# ST_LINK_V2.net
KiCad netlist of a schematic drawn in Altium Designer
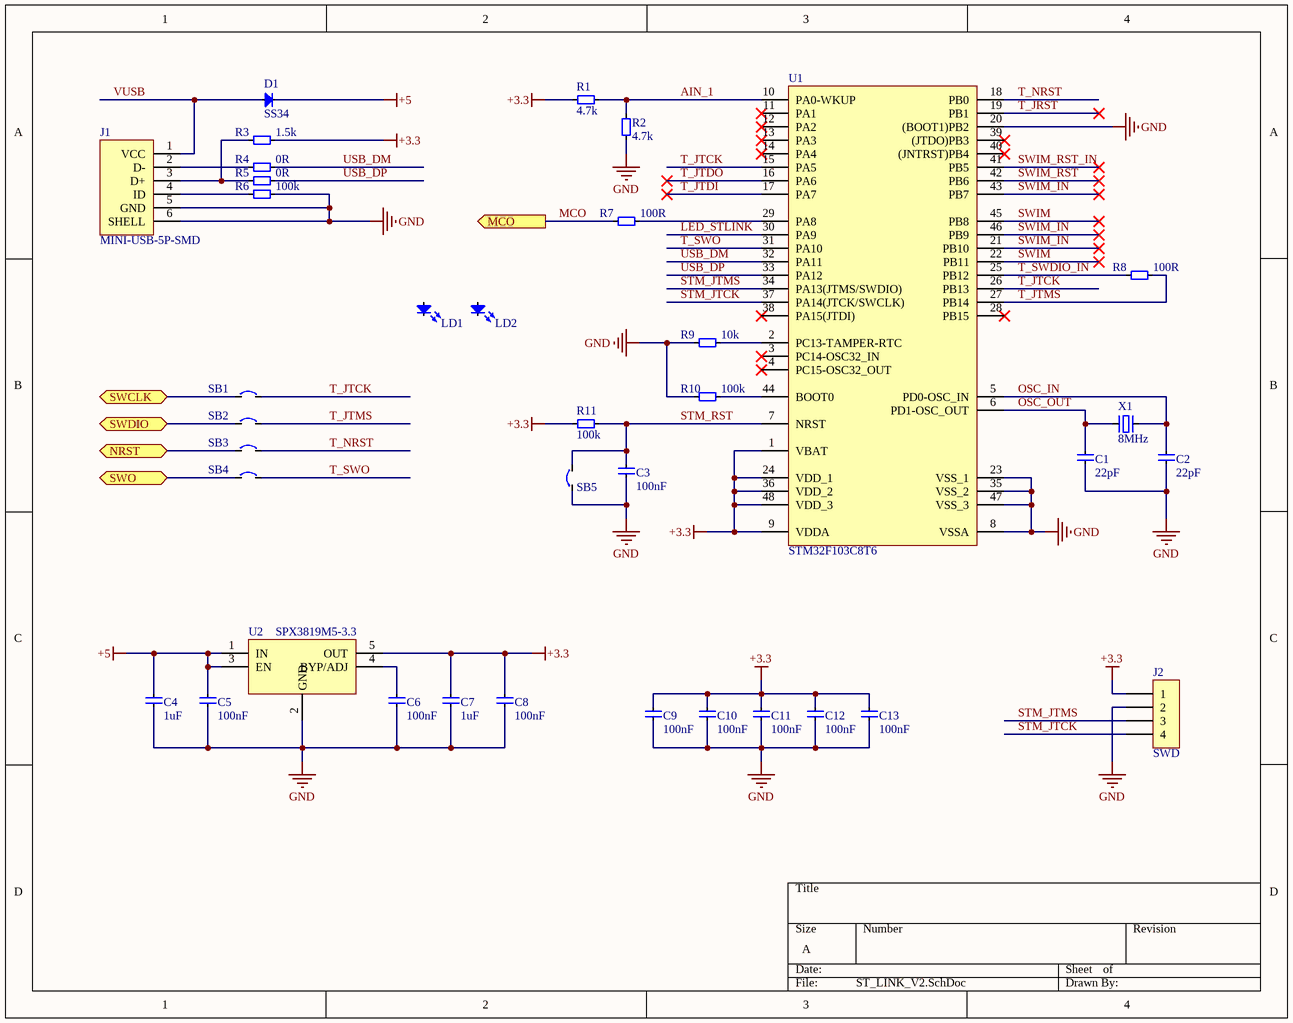
[diagram p0: ST_LINK_V2.SchDoc]

(export (version "E")
  (design (tool "Eeschema 10.0.6"))
  (components
    (comp (ref "C1")
      (value "22pF")
      (footprint "C0805")
      (description "Cac Loai Tu Khong Phan Cuc")
      (libsource (lib "phatvu1294_Lib") (part "CAP"))
    )
    (comp (ref "C2")
      (value "22pF")
      (footprint "C0805")
      (description "Cac Loai Tu Khong Phan Cuc")
      (libsource (lib "phatvu1294_Lib") (part "CAP"))
    )
    (comp (ref "C3")
      (value "100nF")
      (footprint "C0805")
      (description "Cac Loai Tu Khong Phan Cuc")
      (libsource (lib "phatvu1294_Lib") (part "CAP"))
    )
    (comp (ref "C4")
      (value "1uF")
      (footprint "C1206")
      (description "Cac Loai Tu Khong Phan Cuc")
      (libsource (lib "phatvu1294_Lib") (part "CAP"))
    )
    (comp (ref "C5")
      (value "100nF")
      (footprint "C0805")
      (description "Cac Loai Tu Khong Phan Cuc")
      (libsource (lib "phatvu1294_Lib") (part "CAP"))
    )
    (comp (ref "C6")
      (value "100nF")
      (footprint "C0805")
      (description "Cac Loai Tu Khong Phan Cuc")
      (libsource (lib "phatvu1294_Lib") (part "CAP"))
    )
    (comp (ref "C7")
      (value "1uF")
      (footprint "C1206")
      (description "Cac Loai Tu Khong Phan Cuc")
      (libsource (lib "phatvu1294_Lib") (part "CAP"))
    )
    (comp (ref "C8")
      (value "100nF")
      (footprint "C0805")
      (description "Cac Loai Tu Khong Phan Cuc")
      (libsource (lib "phatvu1294_Lib") (part "CAP"))
    )
    (comp (ref "C9")
      (value "100nF")
      (footprint "C0805")
      (description "Cac Loai Tu Khong Phan Cuc")
      (libsource (lib "phatvu1294_Lib") (part "CAP"))
    )
    (comp (ref "C10")
      (value "100nF")
      (footprint "C0805")
      (description "Cac Loai Tu Khong Phan Cuc")
      (libsource (lib "phatvu1294_Lib") (part "CAP"))
    )
    (comp (ref "C11")
      (value "100nF")
      (footprint "C0805")
      (description "Cac Loai Tu Khong Phan Cuc")
      (libsource (lib "phatvu1294_Lib") (part "CAP"))
    )
    (comp (ref "C12")
      (value "100nF")
      (footprint "C0805")
      (description "Cac Loai Tu Khong Phan Cuc")
      (libsource (lib "phatvu1294_Lib") (part "CAP"))
    )
    (comp (ref "C13")
      (value "100nF")
      (footprint "C0805")
      (description "Cac Loai Tu Khong Phan Cuc")
      (libsource (lib "phatvu1294_Lib") (part "CAP"))
    )
    (comp (ref "D1")
      (value "SS34")
      (footprint "DO-214AC-SMA")
      (description "Diode Schottky 1N5822 3A 40V Dan")
      (libsource (lib "phatvu1294_Lib") (part "SS34"))
    )
    (comp (ref "J1")
      (value "MINI-USB-5P-SMD")
      (footprint "MINI-USB-5P-SMD")
      (description "Jack Ket Noi Mini USB 5P Dan")
      (libsource (lib "phatvu1294_Lib") (part "MINI-USB-5P-SMD"))
    )
    (comp (ref "J2")
      (value "SWD")
      (footprint "JP1X4M-2.54")
      (description "Jump Don 4 Chan 2.54mm")
      (libsource (lib "phatvu1294_Lib") (part "JP1X4-2.54"))
    )
    (comp (ref "LD1")
      (value "LED")
      (description "LED Dan Cac Loai")
      (libsource (lib "phatvu1294_Lib") (part "LED_SMD"))
    )
    (comp (ref "LD2")
      (value "LED")
      (description "LED Dan Cac Loai")
      (libsource (lib "phatvu1294_Lib") (part "LED_SMD"))
    )
    (comp (ref "R1")
      (value "4.7k")
      (footprint "R0805")
      (description "Cac Loai Dien Tro")
      (libsource (lib "phatvu1294_Lib") (part "RES"))
    )
    (comp (ref "R2")
      (value "4.7k")
      (footprint "R0805")
      (description "Cac Loai Dien Tro")
      (libsource (lib "phatvu1294_Lib") (part "RES"))
    )
    (comp (ref "R3")
      (value "1.5k")
      (footprint "R0805")
      (description "Cac Loai Dien Tro")
      (libsource (lib "phatvu1294_Lib") (part "RES"))
    )
    (comp (ref "R4")
      (value "0R")
      (footprint "R0805")
      (description "Cac Loai Dien Tro")
      (libsource (lib "phatvu1294_Lib") (part "RES"))
    )
    (comp (ref "R5")
      (value "0R")
      (footprint "R0805")
      (description "Cac Loai Dien Tro")
      (libsource (lib "phatvu1294_Lib") (part "RES"))
    )
    (comp (ref "R6")
      (value "100k")
      (footprint "R0805")
      (description "Cac Loai Dien Tro")
      (libsource (lib "phatvu1294_Lib") (part "RES"))
    )
    (comp (ref "R7")
      (value "100R")
      (footprint "R0805")
      (description "Cac Loai Dien Tro")
      (libsource (lib "phatvu1294_Lib") (part "RES"))
    )
    (comp (ref "R8")
      (value "100R")
      (footprint "R0805")
      (description "Cac Loai Dien Tro")
      (libsource (lib "phatvu1294_Lib") (part "RES"))
    )
    (comp (ref "R9")
      (value "10k")
      (footprint "R0805")
      (description "Cac Loai Dien Tro")
      (libsource (lib "phatvu1294_Lib") (part "RES"))
    )
    (comp (ref "R10")
      (value "100k")
      (footprint "R0805")
      (description "Cac Loai Dien Tro")
      (libsource (lib "phatvu1294_Lib") (part "RES"))
    )
    (comp (ref "R11")
      (value "100k")
      (footprint "R0805")
      (description "Cac Loai Dien Tro")
      (libsource (lib "phatvu1294_Lib") (part "RES"))
    )
    (comp (ref "SB1")
      (value "SB2-NO")
      (footprint "SB2-NO-ROUND")
      (description "Jump Noi Thiec 2 Chan Thuong Mo")
      (libsource (lib "phatvu1294_Lib") (part "SB2-NO"))
    )
    (comp (ref "SB2")
      (value "SB2-NO")
      (footprint "SB2-NO-ROUND")
      (description "Jump Noi Thiec 2 Chan Thuong Mo")
      (libsource (lib "phatvu1294_Lib") (part "SB2-NO"))
    )
    (comp (ref "SB3")
      (value "SB2-NO")
      (footprint "SB2-NO-ROUND")
      (description "Jump Noi Thiec 2 Chan Thuong Mo")
      (libsource (lib "phatvu1294_Lib") (part "SB2-NO"))
    )
    (comp (ref "SB4")
      (value "SB2-NO")
      (footprint "SB2-NO-ROUND")
      (description "Jump Noi Thiec 2 Chan Thuong Mo")
      (libsource (lib "phatvu1294_Lib") (part "SB2-NO"))
    )
    (comp (ref "SB5")
      (value "SB2-NO")
      (footprint "SB2-NO-ROUND")
      (description "Jump Noi Thiec 2 Chan Thuong Mo")
      (libsource (lib "phatvu1294_Lib") (part "SB2-NO"))
    )
    (comp (ref "U1")
      (value "STM32F103C8T6")
      (footprint "LQFP48-0.5-7X7MM")
      (description "VDK 32-Bit ARM Cortex-M3")
      (libsource (lib "phatvu1294_Lib") (part "STM32F103C8T6"))
    )
    (comp (ref "U2")
      (value "SPX3819M5-3.3")
      (footprint "SOT23-5")
      (description "IC On Ap Tuyen Tinh 500mA")
      (libsource (lib "phatvu1294_Lib") (part "SPX3819M5"))
    )
    (comp (ref "X1")
      (value "8MHz")
      (footprint "XTAL-HC49US")
      (description "Thach Anh 2 Chan HC49")
      (libsource (lib "phatvu1294_Lib") (part "XTAL-HC49"))
    )
  )
  (nets
    (net (code "1") (name "+3.3") (class "Default")
      (node (ref "C10") (pin "1") (pinfunction "1_1") (pintype "passive"))
      (node (ref "C11") (pin "1") (pinfunction "1_1") (pintype "passive"))
      (node (ref "C12") (pin "1") (pinfunction "1_1") (pintype "passive"))
      (node (ref "C13") (pin "1") (pinfunction "1_1") (pintype "passive"))
      (node (ref "C7") (pin "1") (pinfunction "1_1") (pintype "passive"))
      (node (ref "C8") (pin "1") (pinfunction "1_1") (pintype "passive"))
      (node (ref "C9") (pin "1") (pinfunction "1_1") (pintype "passive"))
      (node (ref "J2") (pin "1") (pinfunction "1_1") (pintype "passive"))
      (node (ref "R1") (pin "2") (pinfunction "2_2") (pintype "passive"))
      (node (ref "R11") (pin "2") (pinfunction "2_2") (pintype "passive"))
      (node (ref "R3") (pin "2") (pinfunction "2_2") (pintype "passive"))
      (node (ref "U1") (pin "1") (pinfunction "VBAT_1") (pintype "power_in"))
      (node (ref "U1") (pin "24") (pinfunction "VDD_1_24") (pintype "power_in"))
      (node (ref "U1") (pin "36") (pinfunction "VDD_2_36") (pintype "power_in"))
      (node (ref "U1") (pin "48") (pinfunction "VDD_3_48") (pintype "power_in"))
      (node (ref "U1") (pin "9") (pinfunction "VDDA_9") (pintype "power_in"))
      (node (ref "U2") (pin "5") (pinfunction "OUT_5") (pintype "power_in"))
    )
    (net (code "2") (name "+5") (class "Default")
      (node (ref "C4") (pin "1") (pinfunction "1_1") (pintype "passive"))
      (node (ref "C5") (pin "1") (pinfunction "1_1") (pintype "passive"))
      (node (ref "D1") (pin "1") (pinfunction "1_1") (pintype "passive"))
      (node (ref "U2") (pin "1") (pinfunction "IN_1") (pintype "power_in"))
      (node (ref "U2") (pin "3") (pinfunction "EN_3") (pintype "passive"))
    )
    (net (code "3") (name "/AIN_1") (class "Default")
      (node (ref "R1") (pin "1") (pinfunction "1_1") (pintype "passive"))
      (node (ref "R2") (pin "2") (pinfunction "2_2") (pintype "passive"))
      (node (ref "U1") (pin "10") (pinfunction "PA0-WKUP_10") (pintype "passive"))
    )
    (net (code "4") (name "/LED_STLINK") (class "Default")
      (node (ref "U1") (pin "30") (pinfunction "PA9_30") (pintype "passive"))
    )
    (net (code "5") (name "/MCO") (class "Default")
      (node (ref "R7") (pin "2") (pinfunction "2_2") (pintype "passive"))
    )
    (net (code "6") (name "/NRST") (class "Default")
      (node (ref "SB3") (pin "1") (pinfunction "1_1") (pintype "passive"))
    )
    (net (code "7") (name "/OSC_IN") (class "Default")
      (node (ref "C2") (pin "2") (pinfunction "2_2") (pintype "passive"))
      (node (ref "U1") (pin "5") (pinfunction "PD0-OSC_IN_5") (pintype "passive"))
      (node (ref "X1") (pin "1") (pinfunction "1_1") (pintype "passive"))
    )
    (net (code "8") (name "/OSC_OUT") (class "Default")
      (node (ref "C1") (pin "2") (pinfunction "2_2") (pintype "passive"))
      (node (ref "U1") (pin "6") (pinfunction "PD1-OSC_OUT_6") (pintype "passive"))
      (node (ref "X1") (pin "2") (pinfunction "2_2") (pintype "passive"))
    )
    (net (code "9") (name "/STM_JTCK") (class "Default")
      (node (ref "J2") (pin "4") (pinfunction "4_4") (pintype "passive"))
      (node (ref "U1") (pin "37") (pinfunction "PA14(JTCK/SWCLK)_37") (pintype "passive"))
    )
    (net (code "10") (name "/STM_JTMS") (class "Default")
      (node (ref "J2") (pin "3") (pinfunction "3_3") (pintype "passive"))
      (node (ref "U1") (pin "34") (pinfunction "PA13(JTMS/SWDIO)_34") (pintype "passive"))
    )
    (net (code "11") (name "/STM_RST") (class "Default")
      (node (ref "C3") (pin "2") (pinfunction "2_2") (pintype "passive"))
      (node (ref "R11") (pin "1") (pinfunction "1_1") (pintype "passive"))
      (node (ref "SB5") (pin "2") (pinfunction "2_2") (pintype "passive"))
      (node (ref "U1") (pin "7") (pinfunction "NRST_7") (pintype "passive"))
    )
    (net (code "12") (name "/SWCLK") (class "Default")
      (node (ref "SB1") (pin "1") (pinfunction "1_1") (pintype "passive"))
    )
    (net (code "13") (name "/SWDIO") (class "Default")
      (node (ref "SB2") (pin "1") (pinfunction "1_1") (pintype "passive"))
    )
    (net (code "14") (name "/SWIM") (class "Default")
      (node (ref "U1") (pin "22") (pinfunction "PB11_22") (pintype "passive"))
      (node (ref "U1") (pin "45") (pinfunction "PB8_45") (pintype "passive"))
    )
    (net (code "15") (name "/SWIM_IN") (class "Default")
      (node (ref "U1") (pin "21") (pinfunction "PB10_21") (pintype "passive"))
      (node (ref "U1") (pin "43") (pinfunction "PB7_43") (pintype "passive"))
      (node (ref "U1") (pin "46") (pinfunction "PB9_46") (pintype "passive"))
    )
    (net (code "16") (name "/SWIM_RST") (class "Default")
      (node (ref "U1") (pin "42") (pinfunction "PB6_42") (pintype "passive+no_connect"))
    )
    (net (code "17") (name "/SWIM_RST_IN") (class "Default")
      (node (ref "U1") (pin "41") (pinfunction "PB5_41") (pintype "passive+no_connect"))
    )
    (net (code "18") (name "/SWO") (class "Default")
      (node (ref "SB4") (pin "1") (pinfunction "1_1") (pintype "passive"))
    )
    (net (code "19") (name "/T_JRST") (class "Default")
      (node (ref "U1") (pin "19") (pinfunction "PB1_19") (pintype "passive+no_connect"))
    )
    (net (code "20") (name "/T_JTCK") (class "Default")
      (node (ref "SB1") (pin "2") (pinfunction "2_2") (pintype "passive"))
      (node (ref "U1") (pin "15") (pinfunction "PA5_15") (pintype "passive"))
      (node (ref "U1") (pin "26") (pinfunction "PB13_26") (pintype "passive"))
    )
    (net (code "21") (name "/T_JTDI") (class "Default")
      (node (ref "U1") (pin "17") (pinfunction "PA7_17") (pintype "passive+no_connect"))
    )
    (net (code "22") (name "/T_JTDO") (class "Default")
      (node (ref "U1") (pin "16") (pinfunction "PA6_16") (pintype "passive+no_connect"))
    )
    (net (code "23") (name "/T_JTMS") (class "Default")
      (node (ref "R8") (pin "1") (pinfunction "1_1") (pintype "passive"))
      (node (ref "SB2") (pin "2") (pinfunction "2_2") (pintype "passive"))
      (node (ref "U1") (pin "27") (pinfunction "PB14_27") (pintype "passive"))
    )
    (net (code "24") (name "/T_NRST") (class "Default")
      (node (ref "SB3") (pin "2") (pinfunction "2_2") (pintype "passive"))
      (node (ref "U1") (pin "18") (pinfunction "PB0_18") (pintype "passive"))
    )
    (net (code "25") (name "/T_SWDIO_IN") (class "Default")
      (node (ref "R8") (pin "2") (pinfunction "2_2") (pintype "passive"))
      (node (ref "U1") (pin "25") (pinfunction "PB12_25") (pintype "passive"))
    )
    (net (code "26") (name "/T_SWO") (class "Default")
      (node (ref "SB4") (pin "2") (pinfunction "2_2") (pintype "passive"))
      (node (ref "U1") (pin "31") (pinfunction "PA10_31") (pintype "passive"))
    )
    (net (code "27") (name "/USB_DM") (class "Default")
      (node (ref "R4") (pin "2") (pinfunction "2_2") (pintype "passive"))
      (node (ref "U1") (pin "32") (pinfunction "PA11_32") (pintype "passive"))
    )
    (net (code "28") (name "/USB_DP") (class "Default")
      (node (ref "R5") (pin "2") (pinfunction "2_2") (pintype "passive"))
      (node (ref "U1") (pin "33") (pinfunction "PA12_33") (pintype "passive"))
    )
    (net (code "29") (name "/VUSB") (class "Default")
      (node (ref "D1") (pin "2") (pinfunction "2_2") (pintype "passive"))
      (node (ref "J1") (pin "1") (pinfunction "VCC_1") (pintype "passive"))
    )
    (net (code "30") (name "GND") (class "Default")
      (node (ref "C1") (pin "1") (pinfunction "1_1") (pintype "passive"))
      (node (ref "C10") (pin "2") (pinfunction "2_2") (pintype "passive"))
      (node (ref "C11") (pin "2") (pinfunction "2_2") (pintype "passive"))
      (node (ref "C12") (pin "2") (pinfunction "2_2") (pintype "passive"))
      (node (ref "C13") (pin "2") (pinfunction "2_2") (pintype "passive"))
      (node (ref "C2") (pin "1") (pinfunction "1_1") (pintype "passive"))
      (node (ref "C3") (pin "1") (pinfunction "1_1") (pintype "passive"))
      (node (ref "C4") (pin "2") (pinfunction "2_2") (pintype "passive"))
      (node (ref "C5") (pin "2") (pinfunction "2_2") (pintype "passive"))
      (node (ref "C6") (pin "1") (pinfunction "1_1") (pintype "passive"))
      (node (ref "C7") (pin "2") (pinfunction "2_2") (pintype "passive"))
      (node (ref "C8") (pin "2") (pinfunction "2_2") (pintype "passive"))
      (node (ref "C9") (pin "2") (pinfunction "2_2") (pintype "passive"))
      (node (ref "J1") (pin "5") (pinfunction "GND_5") (pintype "passive"))
      (node (ref "J1") (pin "6") (pinfunction "SHELL_6") (pintype "passive"))
      (node (ref "J2") (pin "2") (pinfunction "2_2") (pintype "passive"))
      (node (ref "R10") (pin "2") (pinfunction "2_2") (pintype "passive"))
      (node (ref "R2") (pin "1") (pinfunction "1_1") (pintype "passive"))
      (node (ref "R6") (pin "2") (pinfunction "2_2") (pintype "passive"))
      (node (ref "R9") (pin "2") (pinfunction "2_2") (pintype "passive"))
      (node (ref "SB5") (pin "1") (pinfunction "1_1") (pintype "passive"))
      (node (ref "U1") (pin "20") (pinfunction "(BOOT1)PB2_20") (pintype "passive"))
      (node (ref "U1") (pin "23") (pinfunction "VSS_1_23") (pintype "power_in"))
      (node (ref "U1") (pin "35") (pinfunction "VSS_2_35") (pintype "power_in"))
      (node (ref "U1") (pin "47") (pinfunction "VSS_3_47") (pintype "power_in"))
      (node (ref "U1") (pin "8") (pinfunction "VSSA_8") (pintype "power_in"))
      (node (ref "U2") (pin "2") (pinfunction "GND_2") (pintype "power_in"))
    )
    (net (code "31") (name "Net-(J1-D+)") (class "Default")
      (node (ref "J1") (pin "3") (pinfunction "D+_3") (pintype "passive"))
      (node (ref "R3") (pin "1") (pinfunction "1_1") (pintype "passive"))
      (node (ref "R5") (pin "1") (pinfunction "1_1") (pintype "passive"))
    )
    (net (code "32") (name "Net-(J1-D-)") (class "Default")
      (node (ref "J1") (pin "2") (pinfunction "D-_2") (pintype "passive"))
      (node (ref "R4") (pin "1") (pinfunction "1_1") (pintype "passive"))
    )
    (net (code "33") (name "Net-(J1-ID)") (class "Default")
      (node (ref "J1") (pin "4") (pinfunction "ID_4") (pintype "passive"))
      (node (ref "R6") (pin "1") (pinfunction "1_1") (pintype "passive"))
    )
    (net (code "34") (name "Net-(U1-BOOT0)") (class "Default")
      (node (ref "R10") (pin "1") (pinfunction "1_1") (pintype "passive"))
      (node (ref "U1") (pin "44") (pinfunction "BOOT0_44") (pintype "passive"))
    )
    (net (code "35") (name "Net-(U1-PA8)") (class "Default")
      (node (ref "R7") (pin "1") (pinfunction "1_1") (pintype "passive"))
      (node (ref "U1") (pin "29") (pinfunction "PA8_29") (pintype "passive"))
    )
    (net (code "36") (name "Net-(U1-PC13-TAMPER-RTC)") (class "Default")
      (node (ref "R9") (pin "1") (pinfunction "1_1") (pintype "passive"))
      (node (ref "U1") (pin "2") (pinfunction "PC13-TAMPER-RTC_2") (pintype "passive"))
    )
    (net (code "37") (name "Net-(U2-BYP{slash}ADJ)") (class "Default")
      (node (ref "C6") (pin "2") (pinfunction "2_2") (pintype "passive"))
      (node (ref "U2") (pin "4") (pinfunction "BYP/ADJ_4") (pintype "passive"))
    )
    (net (code "38") (name "unconnected-(LD1-Pad1)") (class "Default")
      (node (ref "LD1") (pin "1") (pinfunction "1_1") (pintype "passive"))
    )
    (net (code "39") (name "unconnected-(LD1-Pad2)") (class "Default")
      (node (ref "LD1") (pin "2") (pinfunction "2_2") (pintype "passive"))
    )
    (net (code "40") (name "unconnected-(LD2-Pad1)") (class "Default")
      (node (ref "LD2") (pin "1") (pinfunction "1_1") (pintype "passive"))
    )
    (net (code "41") (name "unconnected-(LD2-Pad2)") (class "Default")
      (node (ref "LD2") (pin "2") (pinfunction "2_2") (pintype "passive"))
    )
    (net (code "42") (name "unconnected-(U1-(JNTRST)PB4-Pad40)") (class "Default")
      (node (ref "U1") (pin "40") (pinfunction "(JNTRST)PB4_40") (pintype "passive+no_connect"))
    )
    (net (code "43") (name "unconnected-(U1-(JTDO)PB3-Pad39)") (class "Default")
      (node (ref "U1") (pin "39") (pinfunction "(JTDO)PB3_39") (pintype "passive+no_connect"))
    )
    (net (code "44") (name "unconnected-(U1-PA1-Pad11)") (class "Default")
      (node (ref "U1") (pin "11") (pinfunction "PA1_11") (pintype "passive+no_connect"))
    )
    (net (code "45") (name "unconnected-(U1-PA2-Pad12)") (class "Default")
      (node (ref "U1") (pin "12") (pinfunction "PA2_12") (pintype "passive+no_connect"))
    )
    (net (code "46") (name "unconnected-(U1-PA3-Pad13)") (class "Default")
      (node (ref "U1") (pin "13") (pinfunction "PA3_13") (pintype "passive+no_connect"))
    )
    (net (code "47") (name "unconnected-(U1-PA4-Pad14)") (class "Default")
      (node (ref "U1") (pin "14") (pinfunction "PA4_14") (pintype "passive+no_connect"))
    )
    (net (code "48") (name "unconnected-(U1-PA15(JTDI)-Pad38)") (class "Default")
      (node (ref "U1") (pin "38") (pinfunction "PA15(JTDI)_38") (pintype "passive+no_connect"))
    )
    (net (code "49") (name "unconnected-(U1-PB15-Pad28)") (class "Default")
      (node (ref "U1") (pin "28") (pinfunction "PB15_28") (pintype "passive+no_connect"))
    )
    (net (code "50") (name "unconnected-(U1-PC14-OSC32_IN-Pad3)") (class "Default")
      (node (ref "U1") (pin "3") (pinfunction "PC14-OSC32_IN_3") (pintype "passive+no_connect"))
    )
    (net (code "51") (name "unconnected-(U1-PC15-OSC32_OUT-Pad4)") (class "Default")
      (node (ref "U1") (pin "4") (pinfunction "PC15-OSC32_OUT_4") (pintype "passive+no_connect"))
    )
  )
)
